# USB.net
KiCad netlist of a schematic drawn in Altium Designer
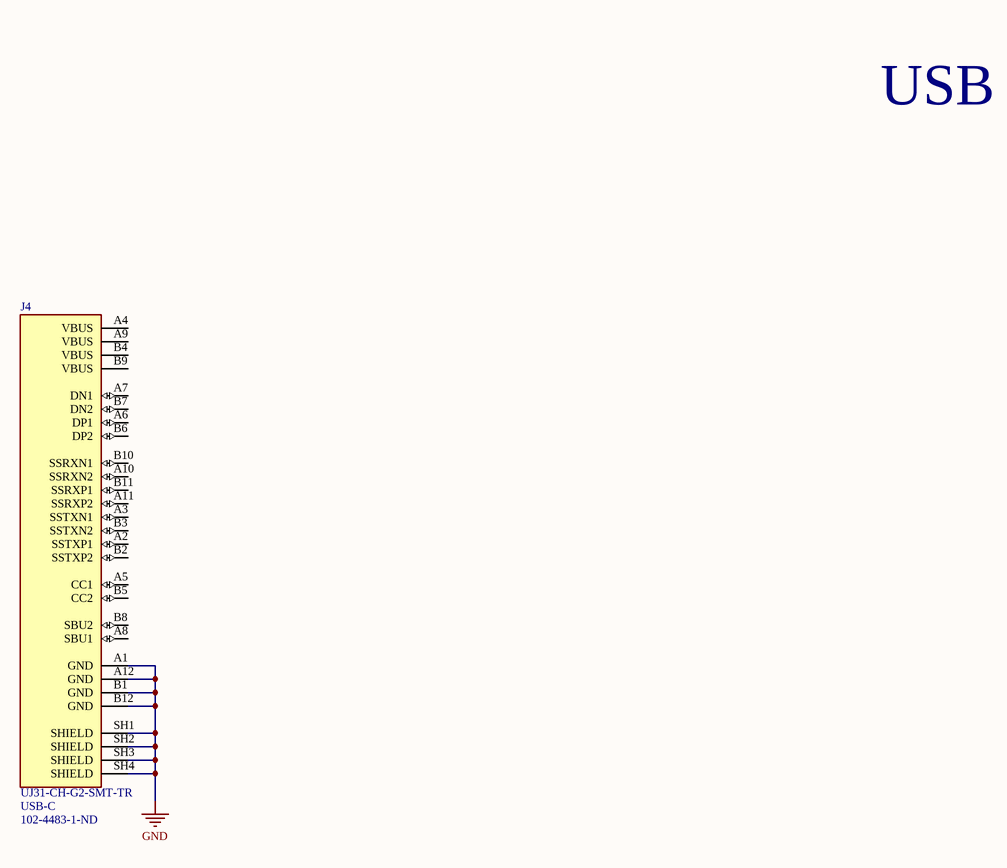
[diagram p0: USB.SchDoc]

(export (version "E")
  (design (tool "Eeschema 10.0.6"))
  (components
    (comp (ref "J4")
      (value "UJ31-CH-G2-SMT-TR")
      (footprint "UJ31-CH-G2-SMT-TR")
      (description "Type C, USB 3.1 Gen 2, 5 A, Right Angle, Surface Mount _SMT_, USB Receptacle")
      (fields
        (field (name "MFR") "CUI Devices")
        (field (name "DIGIKEY PART NUMBER") "102-4483-1-ND")
        (field (name "CONNECTOR TYPE") "USB-C")
        (field (name "SUPPLIER PART NUMBER 1") "102-4483-1-ND")
      )
      (libsource (lib "CryptLib") (part "CONN_UJ31-CH-G2-SMT-TR"))
    )
  )
  (nets
    (net (code "1") (name "GND") (class "Default")
      (node (ref "J4") (pin "A1") (pinfunction "GND_A1") (pintype "power_in"))
      (node (ref "J4") (pin "A12") (pinfunction "GND_A12") (pintype "power_in"))
      (node (ref "J4") (pin "B1") (pinfunction "GND_B1") (pintype "power_in"))
      (node (ref "J4") (pin "B12") (pinfunction "GND_B12") (pintype "power_in"))
      (node (ref "J4") (pin "SH1") (pinfunction "SHIELD_SH1") (pintype "power_in"))
      (node (ref "J4") (pin "SH2") (pinfunction "SHIELD_SH2") (pintype "power_in"))
      (node (ref "J4") (pin "SH3") (pinfunction "SHIELD_SH3") (pintype "power_in"))
      (node (ref "J4") (pin "SH4") (pinfunction "SHIELD_SH4") (pintype "power_in"))
    )
    (net (code "2") (name "unconnected-(J4-CC1-PadA5)") (class "Default")
      (node (ref "J4") (pin "A5") (pinfunction "CC1_A5") (pintype "bidirectional"))
    )
    (net (code "3") (name "unconnected-(J4-CC2-PadB5)") (class "Default")
      (node (ref "J4") (pin "B5") (pinfunction "CC2_B5") (pintype "bidirectional"))
    )
    (net (code "4") (name "unconnected-(J4-DN1-PadA7)") (class "Default")
      (node (ref "J4") (pin "A7") (pinfunction "DN1_A7") (pintype "bidirectional"))
    )
    (net (code "5") (name "unconnected-(J4-DN2-PadB7)") (class "Default")
      (node (ref "J4") (pin "B7") (pinfunction "DN2_B7") (pintype "bidirectional"))
    )
    (net (code "6") (name "unconnected-(J4-DP1-PadA6)") (class "Default")
      (node (ref "J4") (pin "A6") (pinfunction "DP1_A6") (pintype "bidirectional"))
    )
    (net (code "7") (name "unconnected-(J4-DP2-PadB6)") (class "Default")
      (node (ref "J4") (pin "B6") (pinfunction "DP2_B6") (pintype "bidirectional"))
    )
    (net (code "8") (name "unconnected-(J4-SBU1-PadA8)") (class "Default")
      (node (ref "J4") (pin "A8") (pinfunction "SBU1_A8") (pintype "bidirectional"))
    )
    (net (code "9") (name "unconnected-(J4-SBU2-PadB8)") (class "Default")
      (node (ref "J4") (pin "B8") (pinfunction "SBU2_B8") (pintype "bidirectional"))
    )
    (net (code "10") (name "unconnected-(J4-SSRXN1-PadB10)") (class "Default")
      (node (ref "J4") (pin "B10") (pinfunction "SSRXN1_B10") (pintype "bidirectional"))
    )
    (net (code "11") (name "unconnected-(J4-SSRXN2-PadA10)") (class "Default")
      (node (ref "J4") (pin "A10") (pinfunction "SSRXN2_A10") (pintype "bidirectional"))
    )
    (net (code "12") (name "unconnected-(J4-SSRXP1-PadB11)") (class "Default")
      (node (ref "J4") (pin "B11") (pinfunction "SSRXP1_B11") (pintype "bidirectional"))
    )
    (net (code "13") (name "unconnected-(J4-SSRXP2-PadA11)") (class "Default")
      (node (ref "J4") (pin "A11") (pinfunction "SSRXP2_A11") (pintype "bidirectional"))
    )
    (net (code "14") (name "unconnected-(J4-SSTXN1-PadA3)") (class "Default")
      (node (ref "J4") (pin "A3") (pinfunction "SSTXN1_A3") (pintype "bidirectional"))
    )
    (net (code "15") (name "unconnected-(J4-SSTXN2-PadB3)") (class "Default")
      (node (ref "J4") (pin "B3") (pinfunction "SSTXN2_B3") (pintype "bidirectional"))
    )
    (net (code "16") (name "unconnected-(J4-SSTXP1-PadA2)") (class "Default")
      (node (ref "J4") (pin "A2") (pinfunction "SSTXP1_A2") (pintype "bidirectional"))
    )
    (net (code "17") (name "unconnected-(J4-SSTXP2-PadB2)") (class "Default")
      (node (ref "J4") (pin "B2") (pinfunction "SSTXP2_B2") (pintype "bidirectional"))
    )
    (net (code "18") (name "unconnected-(J4-VBUS-PadA4)") (class "Default")
      (node (ref "J4") (pin "A4") (pinfunction "VBUS_A4") (pintype "power_in"))
    )
    (net (code "19") (name "unconnected-(J4-VBUS-PadA9)") (class "Default")
      (node (ref "J4") (pin "A9") (pinfunction "VBUS_A9") (pintype "power_in"))
    )
    (net (code "20") (name "unconnected-(J4-VBUS-PadB4)") (class "Default")
      (node (ref "J4") (pin "B4") (pinfunction "VBUS_B4") (pintype "power_in"))
    )
    (net (code "21") (name "unconnected-(J4-VBUS-PadB9)") (class "Default")
      (node (ref "J4") (pin "B9") (pinfunction "VBUS_B9") (pintype "power_in"))
    )
  )
)
